# BMA400_ACC_LinkitV3.net
KiCad netlist of a schematic drawn in Altium Designer
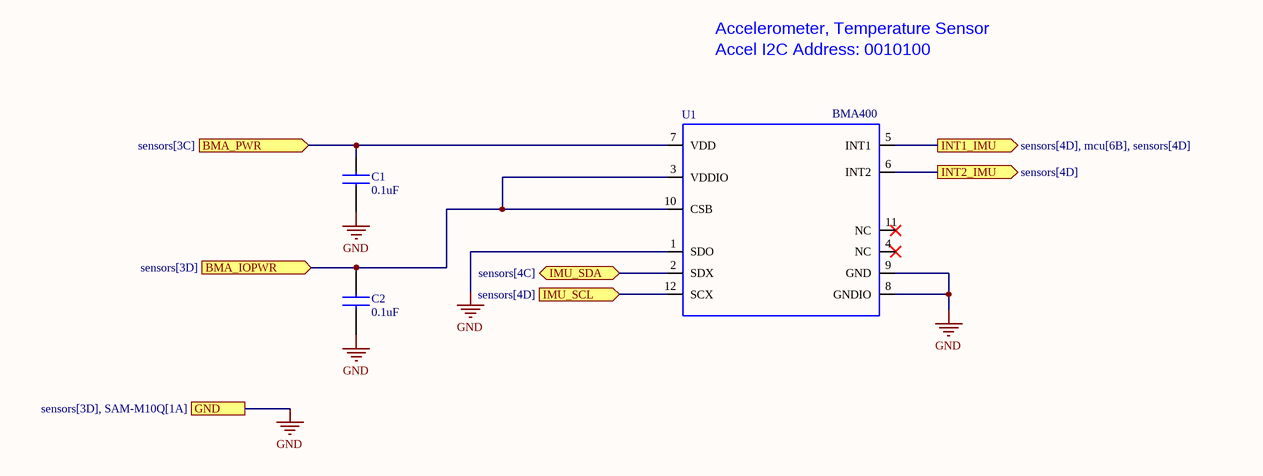
[diagram p0: BMA400_ACC_LinkitV3.SchDoc]

(export (version "E")
  (design (tool "Eeschema 10.0.6"))
  (components
    (comp (ref "C1")
      (value "0.1uF")
      (footprint "CAPC0603X33N")
      (description "Multilayer Ceramic Capacitors MLCC - SMD/SMT .1UF     16V   10%        0201")
      (fields
        (field (name "MOUSER PART NUMBER") "81-GRM033Z71C104KE4D")
        (field (name "MANUFACTURER_PART_NUMBER") "GRM033Z71C104KE14D")
      )
      (libsource (lib "stm32wl-dev") (part "GRM033Z71C104KE14D"))
    )
    (comp (ref "C2")
      (value "0.1uF")
      (footprint "CAPC0603X33N")
      (description "Multilayer Ceramic Capacitors MLCC - SMD/SMT .1UF     16V   10%        0201")
      (fields
        (field (name "MOUSER PART NUMBER") "81-GRM033Z71C104KE4D")
        (field (name "MANUFACTURER_PART_NUMBER") "GRM033Z71C104KE14D")
      )
      (libsource (lib "stm32wl-dev") (part "GRM033Z71C104KE14D"))
    )
    (comp (ref "U1")
      (value "BMA400")
      (footprint "LGA12-BMA400")
      (description "IC AXL Accel/temp SPI/I2C 12LGA")
      (fields (field (name "MANUFACTURER") "Bosch Sensortec"))
      (libsource (lib "Linkit_V3") (part "BMA400"))
    )
  )
  (nets
    (net (code "1") (name "/BMA_IOPWR") (class "Default")
      (node (ref "C2") (pin "2") (pinfunction "2_2") (pintype "passive"))
      (node (ref "U1") (pin "10") (pinfunction "CSB_10") (pintype "passive"))
      (node (ref "U1") (pin "3") (pinfunction "VDDIO_3") (pintype "passive"))
    )
    (net (code "2") (name "/BMA_PWR") (class "Default")
      (node (ref "C1") (pin "2") (pinfunction "2_2") (pintype "passive"))
      (node (ref "U1") (pin "7") (pinfunction "VDD_7") (pintype "passive"))
    )
    (net (code "3") (name "/IMU_SCL") (class "Default")
      (node (ref "U1") (pin "12") (pinfunction "SCX_12") (pintype "passive"))
    )
    (net (code "4") (name "/IMU_SDA") (class "Default")
      (node (ref "U1") (pin "2") (pinfunction "SDX_2") (pintype "passive"))
    )
    (net (code "5") (name "/INT1_IMU") (class "Default")
      (node (ref "U1") (pin "5") (pinfunction "INT1_5") (pintype "passive"))
    )
    (net (code "6") (name "/INT2_IMU") (class "Default")
      (node (ref "U1") (pin "6") (pinfunction "INT2_6") (pintype "passive"))
    )
    (net (code "7") (name "GND") (class "Default")
      (node (ref "C1") (pin "1") (pinfunction "1_1") (pintype "passive"))
      (node (ref "C2") (pin "1") (pinfunction "1_1") (pintype "passive"))
      (node (ref "U1") (pin "1") (pinfunction "SDO_1") (pintype "passive"))
      (node (ref "U1") (pin "8") (pinfunction "GNDIO_8") (pintype "passive"))
      (node (ref "U1") (pin "9") (pinfunction "GND_9") (pintype "passive"))
    )
    (net (code "8") (name "unconnected-(U1-NC-Pad4)") (class "Default")
      (node (ref "U1") (pin "4") (pinfunction "NC_4") (pintype "passive+no_connect"))
    )
    (net (code "9") (name "unconnected-(U1-NC-Pad11)") (class "Default")
      (node (ref "U1") (pin "11") (pinfunction "NC_11") (pintype "passive+no_connect"))
    )
  )
)
